# SCH_IR-rotary-encoder-bruker-trinket_202.net
KiCad netlist of a schematic drawn in EasyEDA
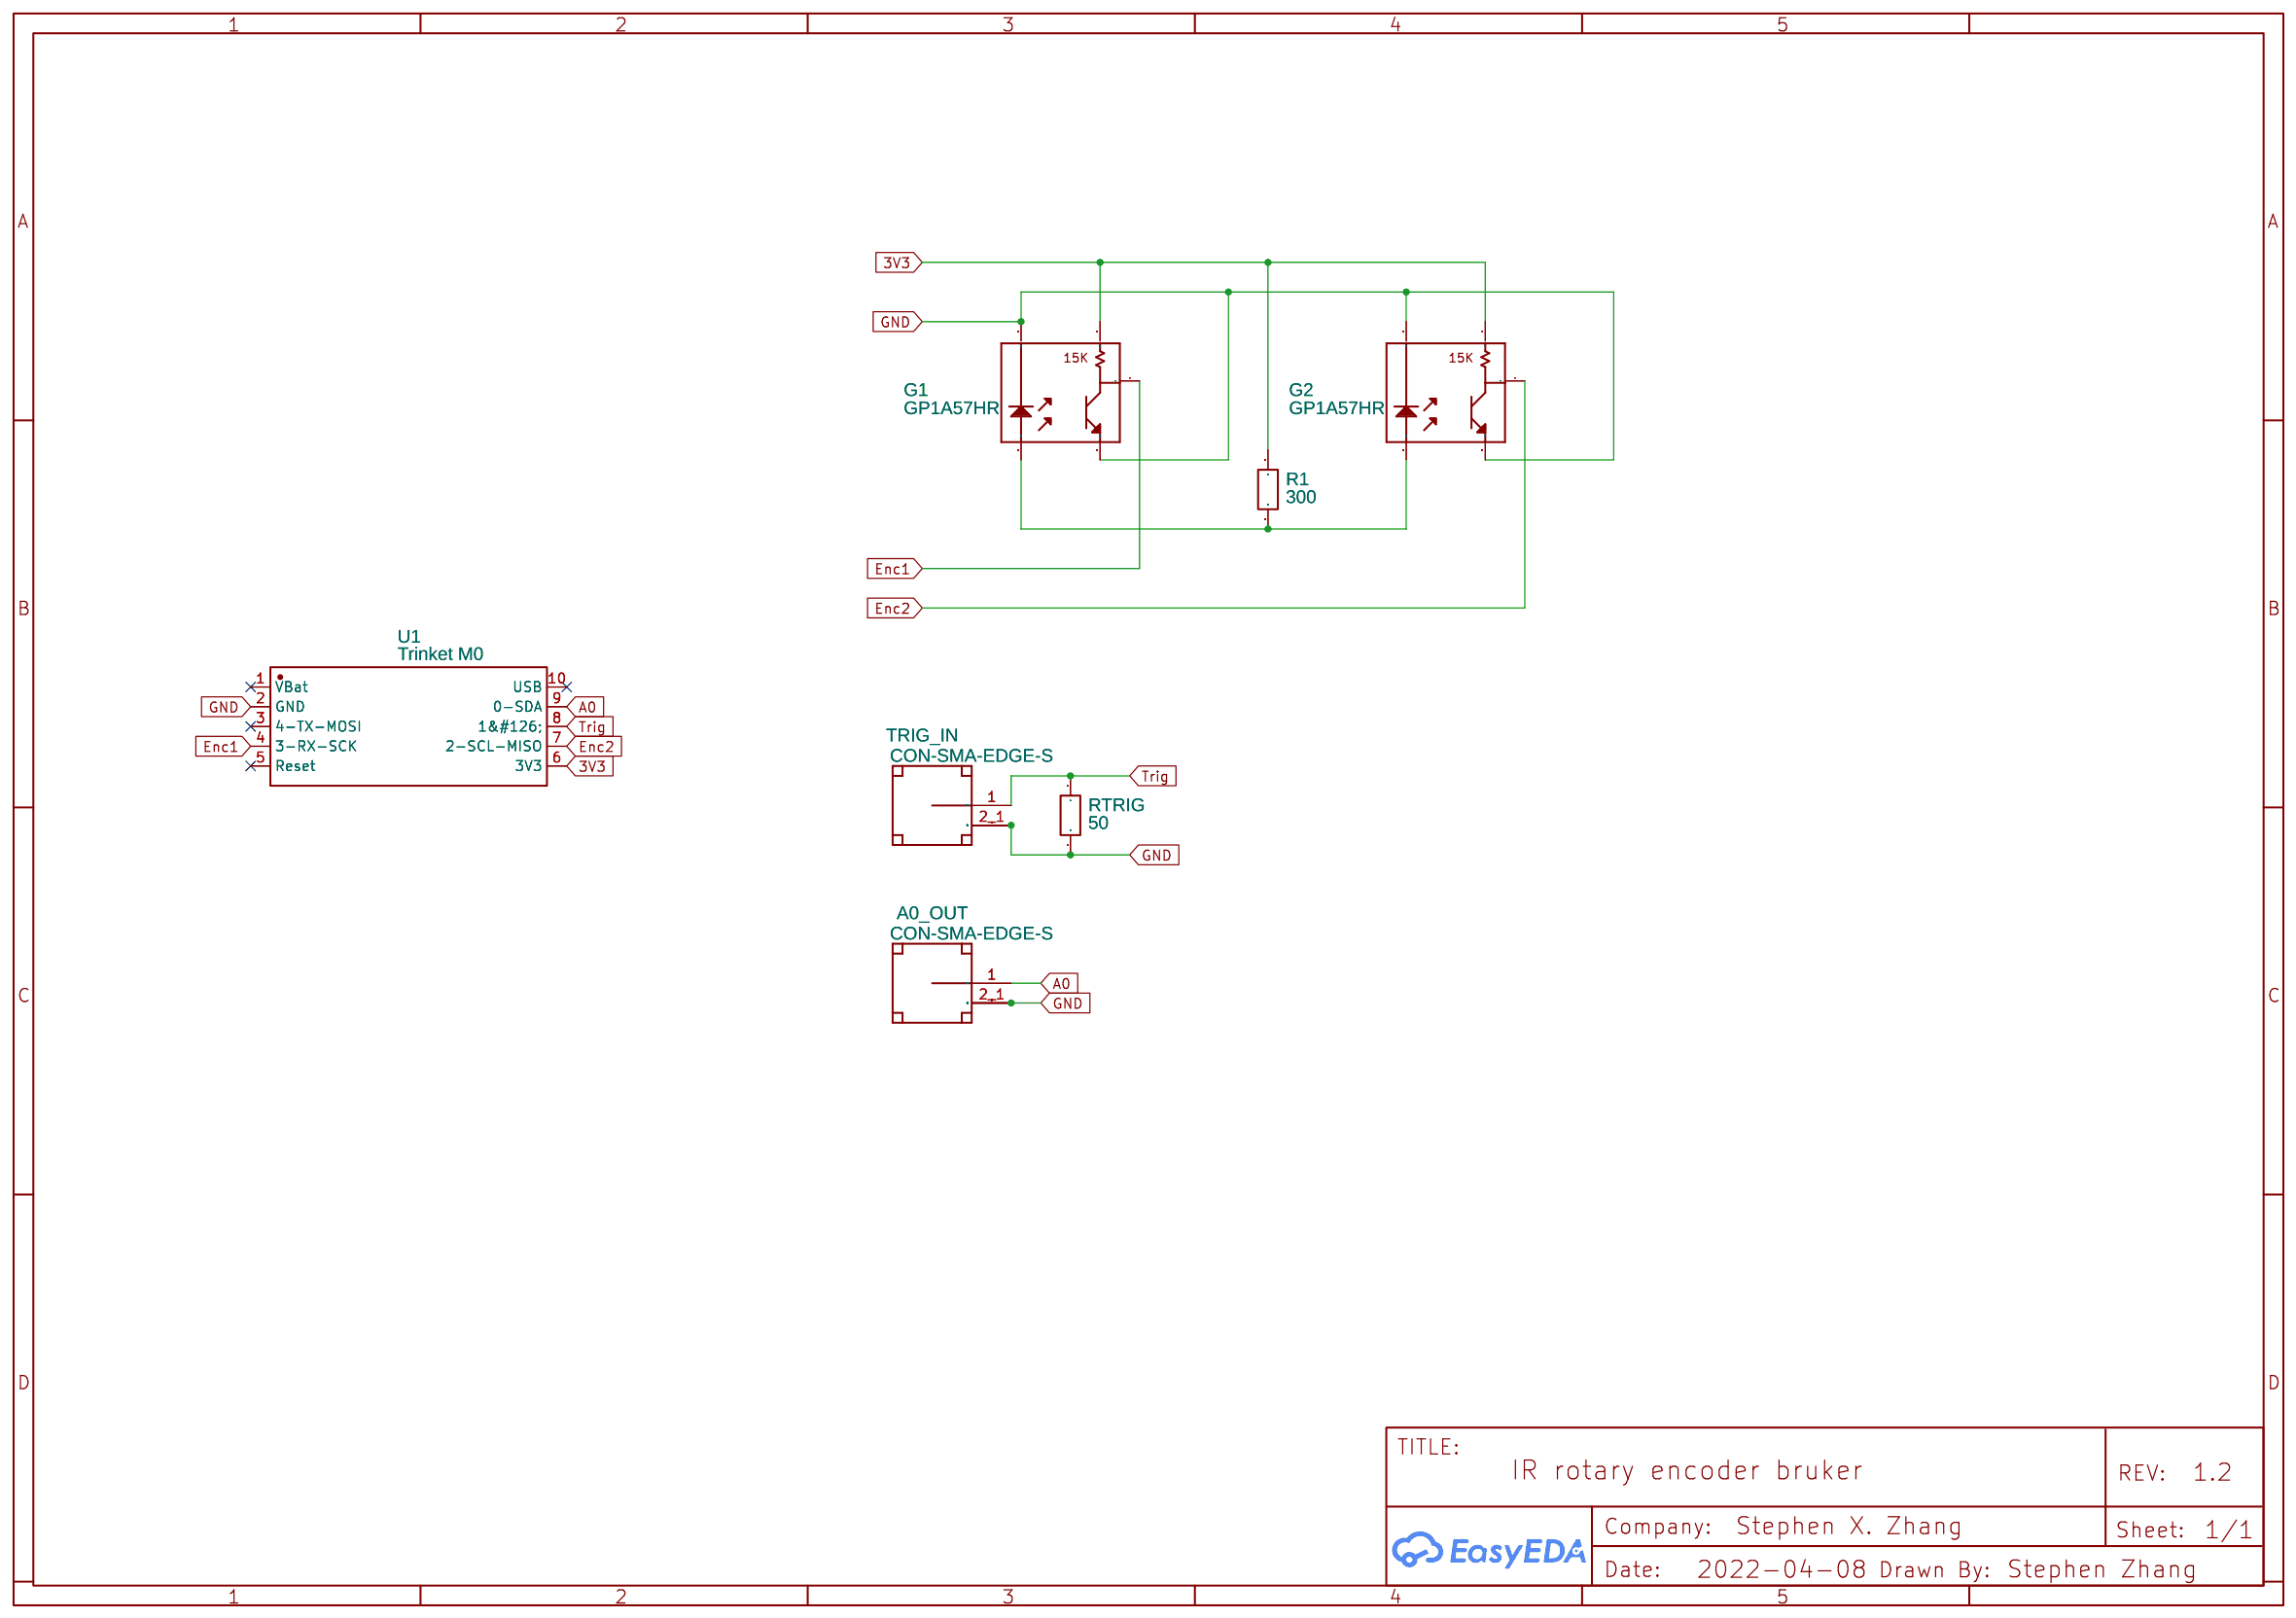
[diagram p0: schematic sheet]

(export (version "E")
  (design (tool "Eeschema 10.0.6"))
  (components
    (comp (ref "A0_OUT") (value "CON-SMA-EDGE-S") (libsource (lib "") (part "CON-SMA-EDGE-S_1")))
    (comp (ref "G1") (value "GP1A57HR") (libsource (lib "") (part "GP1A57HR")))
    (comp (ref "G2") (value "GP1A57HR") (libsource (lib "") (part "GP1A57HR")))
    (comp (ref "R1")
      (value "300")
      (fields
        (field (name "Manufacturer Part") "RD 1/4W 200R J T/B A1")
        (field (name "Manufacturer") "TyoHM")
      )
      (libsource (lib "") (part "RD 1/4W 200R J T/B A1_1"))
    )
    (comp (ref "RTRIG")
      (value "50")
      (fields
        (field (name "Manufacturer Part") "RD 1/4W 200R J T/B A1")
        (field (name "Manufacturer") "TyoHM")
      )
      (libsource (lib "") (part "RD 1/4W 200R J T/B A1"))
    )
    (comp (ref "TRIG_IN") (value "CON-SMA-EDGE-S") (libsource (lib "") (part "CON-SMA-EDGE-S")))
    (comp (ref "U1")
      (value "Trinket M0")
      (fields (field (name "Manufacturer Part") "3500") (field (name "Manufacturer") "Adafruit"))
      (libsource (lib "") (part "Trinket M0"))
    )
  )
  (nets
    (net (code "1") (name "3V3") (class "Default")
      (node (ref "G1") (pin "3") (pinfunction "3_3") (pintype "bidirectional"))
      (node (ref "G2") (pin "3") (pinfunction "3_3") (pintype "bidirectional"))
      (node (ref "R1") (pin "1") (pinfunction "1_1") (pintype "unspecified"))
      (node (ref "U1") (pin "6") (pinfunction "3V3_6") (pintype "unspecified"))
    )
    (net (code "2") (name "A0") (class "Default")
      (node (ref "A0_OUT") (pin "1") (pinfunction "SIGNAL_1") (pintype "bidirectional"))
      (node (ref "U1") (pin "9") (pinfunction "0-SDA_9") (pintype "unspecified"))
    )
    (net (code "3") (name "Enc1") (class "Default")
      (node (ref "G1") (pin "4") (pinfunction "4_4") (pintype "bidirectional"))
      (node (ref "U1") (pin "4") (pinfunction "3-RX-SCK_4") (pintype "unspecified"))
    )
    (net (code "4") (name "Enc2") (class "Default")
      (node (ref "G2") (pin "4") (pinfunction "4_4") (pintype "bidirectional"))
      (node (ref "U1") (pin "7") (pinfunction "2-SCL-MISO_7") (pintype "unspecified"))
    )
    (net (code "5") (name "GND") (class "Default")
      (node (ref "A0_OUT") (pin "2_1") (pinfunction "GND_2_1") (pintype "bidirectional"))
      (node (ref "A0_OUT") (pin "2_2") (pinfunction "GND_2_2") (pintype "bidirectional"))
      (node (ref "A0_OUT") (pin "3_1") (pinfunction "GND_3_1") (pintype "bidirectional"))
      (node (ref "A0_OUT") (pin "3_2") (pinfunction "GND_3_2") (pintype "bidirectional"))
      (node (ref "G1") (pin "2") (pinfunction "2_2") (pintype "bidirectional"))
      (node (ref "G1") (pin "5") (pinfunction "5_5") (pintype "bidirectional"))
      (node (ref "G2") (pin "2") (pinfunction "2_2") (pintype "bidirectional"))
      (node (ref "G2") (pin "5") (pinfunction "5_5") (pintype "bidirectional"))
      (node (ref "RTRIG") (pin "2") (pinfunction "2_2") (pintype "unspecified"))
      (node (ref "TRIG_IN") (pin "2_1") (pinfunction "GND_2_1") (pintype "bidirectional"))
      (node (ref "TRIG_IN") (pin "2_2") (pinfunction "GND_2_2") (pintype "bidirectional"))
      (node (ref "TRIG_IN") (pin "3_1") (pinfunction "GND_3_1") (pintype "bidirectional"))
      (node (ref "TRIG_IN") (pin "3_2") (pinfunction "GND_3_2") (pintype "bidirectional"))
      (node (ref "U1") (pin "2") (pinfunction "GND_2") (pintype "unspecified"))
    )
    (net (code "6") (name "Net-(G1-Pad1)") (class "Default")
      (node (ref "G1") (pin "1") (pinfunction "1_1") (pintype "bidirectional"))
      (node (ref "G2") (pin "1") (pinfunction "1_1") (pintype "bidirectional"))
      (node (ref "R1") (pin "2") (pinfunction "2_2") (pintype "unspecified"))
    )
    (net (code "7") (name "Trig") (class "Default")
      (node (ref "RTRIG") (pin "1") (pinfunction "1_1") (pintype "unspecified"))
      (node (ref "TRIG_IN") (pin "1") (pinfunction "SIGNAL_1") (pintype "bidirectional"))
      (node (ref "U1") (pin "8") (pinfunction "1&#126;_8") (pintype "unspecified"))
    )
    (net (code "8") (name "unconnected-(U1-4-TX-MOSI-Pad3)") (class "Default")
      (node (ref "U1") (pin "3") (pinfunction "4-TX-MOSI_3") (pintype "unspecified+no_connect"))
    )
    (net (code "9") (name "unconnected-(U1-Reset-Pad5)") (class "Default")
      (node (ref "U1") (pin "5") (pinfunction "Reset_5") (pintype "unspecified+no_connect"))
    )
    (net (code "10") (name "unconnected-(U1-USB-Pad10)") (class "Default")
      (node (ref "U1") (pin "10") (pinfunction "USB_10") (pintype "unspecified+no_connect"))
    )
    (net (code "11") (name "unconnected-(U1-VBat-Pad1)") (class "Default")
      (node (ref "U1") (pin "1") (pinfunction "VBat_1") (pintype "unspecified+no_connect"))
    )
  )
)
